# Driver_Controller_Tester.net
KiCad netlist of a schematic drawn in Altium Designer
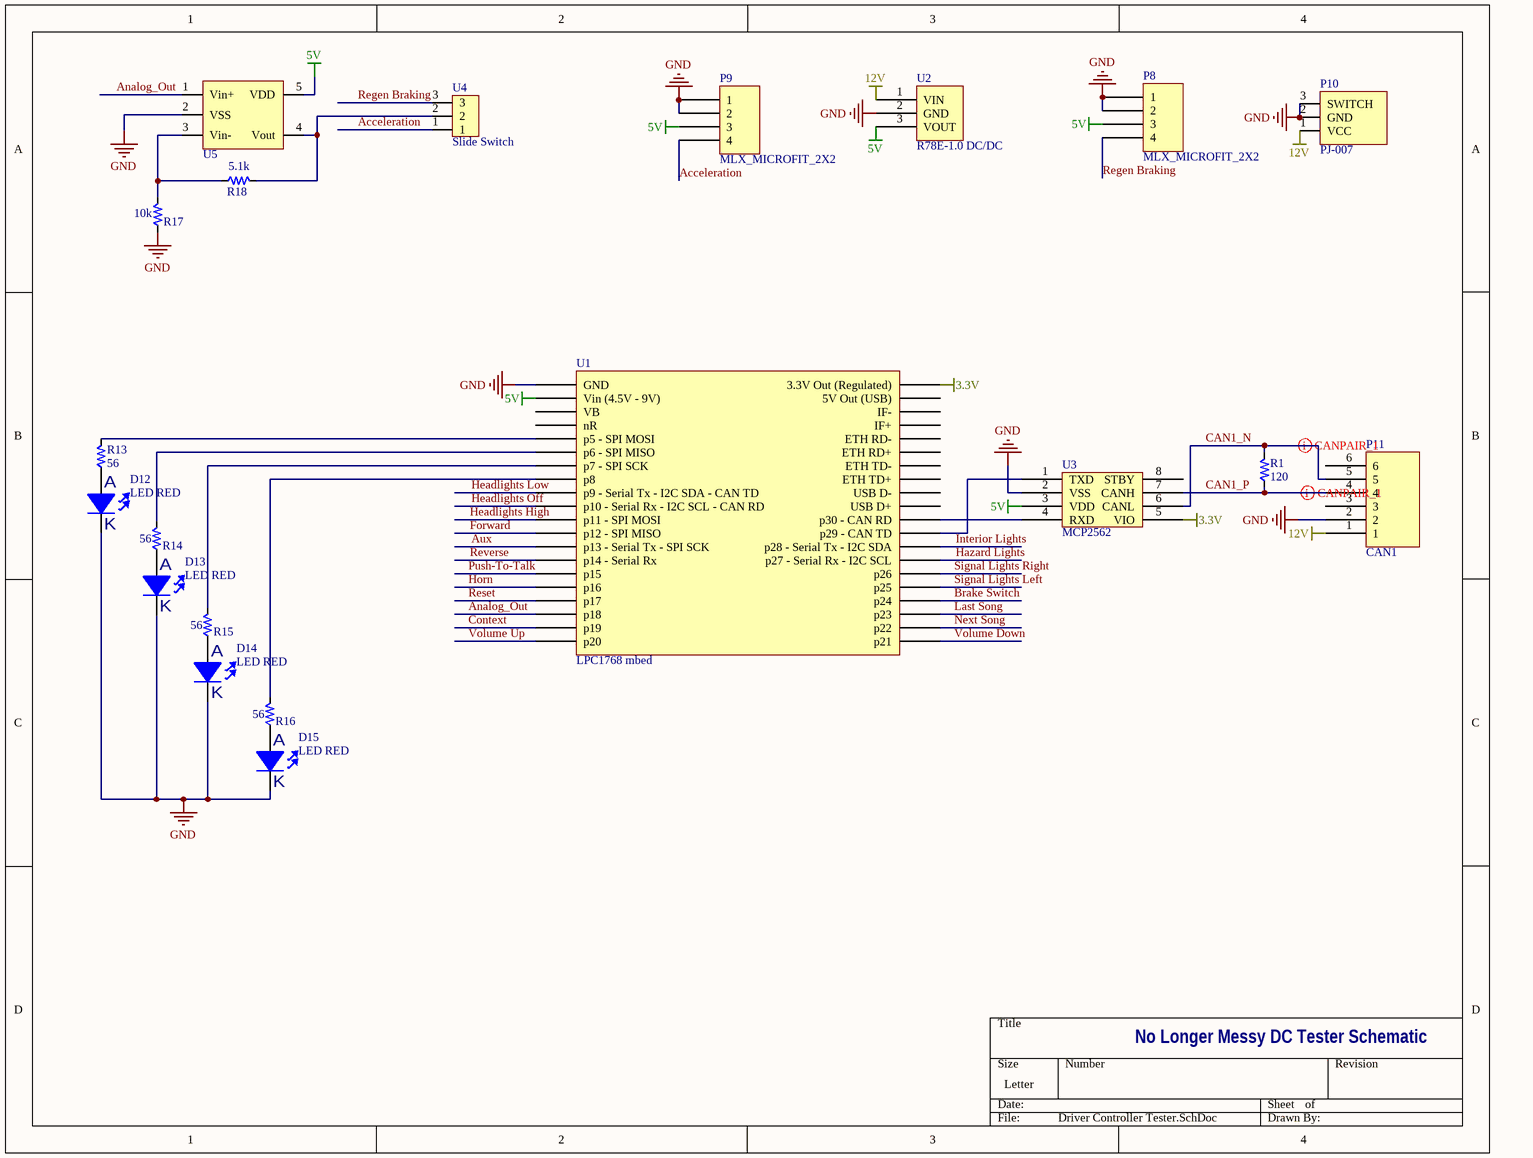
[diagram p0: Driver Controller Tester.SchDoc]

(export (version "E")
  (design (tool "Eeschema 10.0.6"))
  (components
    (comp (ref "D12")
      (value "LED RED")
      (footprint "RED LED")
      (libsource (lib "LED RED 150141RS73100") (part "LED RED"))
    )
    (comp (ref "D13")
      (value "LED RED")
      (footprint "RED LED")
      (libsource (lib "LED RED 150141RS73100") (part "LED RED"))
    )
    (comp (ref "D14")
      (value "LED RED")
      (footprint "RED LED")
      (libsource (lib "LED RED 150141RS73100") (part "LED RED"))
    )
    (comp (ref "D15")
      (value "LED RED")
      (footprint "RED LED")
      (libsource (lib "LED RED 150141RS73100") (part "LED RED"))
    )
    (comp (ref "P8")
      (value "MLX_MICROFIT_2X2")
      (footprint "MLX_MICROFIT_2X2")
      (libsource (lib "MLX_MICROFIT_2X2_SCH") (part "MLX_MICROFIT_2X2"))
    )
    (comp (ref "P9")
      (value "MLX_MICROFIT_2X2")
      (footprint "MLX_MICROFIT_2X2")
      (libsource (lib "MLX_MICROFIT_2X2_SCH") (part "MLX_MICROFIT_2X2"))
    )
    (comp (ref "P10")
      (value "PJ-007")
      (footprint "BARREL JACK PJ007")
      (libsource (lib "BARREL JACK PJ-007") (part "Component_1"))
    )
    (comp (ref "P11")
      (value "CAN1")
      (footprint "PCB_MLX_MICROFIT_3X2")
      (libsource (lib "SCH_MLX_MICROFIT_3X2_P") (part "SCH_MLX_MICROFIT_3X2"))
    )
    (comp (ref "R1")
      (value "120")
      (footprint "PCB_GENERIC_SMD_0603")
      (description "120 Ohms")
      (libsource (lib "SCH_GENERIC_RESISTOR_0603") (part "SCH_GENERIC_RESISTOR_0603"))
    )
    (comp (ref "R13")
      (value "SCH_GENERIC_RESISTOR_0603")
      (footprint "PCB_GENERIC_SMD_0603")
      (description "Generic SMD resistor 0603")
      (fields (field (name "RESISTANCE") "56"))
      (libsource (lib "SCH_GENERIC_RESISTOR_0603") (part "SCH_GENERIC_RESISTOR_0603"))
    )
    (comp (ref "R14")
      (value "SCH_GENERIC_RESISTOR_0603")
      (footprint "PCB_GENERIC_SMD_0603")
      (description "Generic SMD resistor 0603")
      (fields (field (name "RESISTANCE") "56"))
      (libsource (lib "SCH_GENERIC_RESISTOR_0603") (part "SCH_GENERIC_RESISTOR_0603"))
    )
    (comp (ref "R15")
      (value "SCH_GENERIC_RESISTOR_0603")
      (footprint "PCB_GENERIC_SMD_0603")
      (description "Generic SMD resistor 0603")
      (fields (field (name "RESISTANCE") "56"))
      (libsource (lib "SCH_GENERIC_RESISTOR_0603") (part "SCH_GENERIC_RESISTOR_0603"))
    )
    (comp (ref "R16")
      (value "SCH_GENERIC_RESISTOR_0603")
      (footprint "PCB_GENERIC_SMD_0603")
      (description "Generic SMD resistor 0603")
      (fields (field (name "RESISTANCE") "56"))
      (libsource (lib "SCH_GENERIC_RESISTOR_0603") (part "SCH_GENERIC_RESISTOR_0603"))
    )
    (comp (ref "R17")
      (value "SCH_GENERIC_RESISTOR_0603")
      (footprint "PCB_GENERIC_SMD_0603")
      (description "Generic SMD resistor 0603")
      (fields (field (name "RESISTANCE") "10k"))
      (libsource (lib "SCH_GENERIC_RESISTOR_0603") (part "SCH_GENERIC_RESISTOR_0603"))
    )
    (comp (ref "R18")
      (value "SCH_GENERIC_RESISTOR_0603")
      (footprint "PCB_GENERIC_SMD_0603")
      (description "Generic SMD resistor 0603")
      (fields (field (name "RESISTANCE") "5.1k"))
      (libsource (lib "SCH_GENERIC_RESISTOR_0603") (part "SCH_GENERIC_RESISTOR_0603"))
    )
    (comp (ref "U1")
      (value "LPC1768 mbed")
      (footprint "LPC 1768 mbed Layout")
      (libsource (lib "LPC1768_mbed_SCH") (part "LPC1768 mbed"))
    )
    (comp (ref "U2")
      (value "R78E-1.0 DC/DC")
      (footprint "R78-1.0")
      (libsource (lib "R78E-1.0_DCDC_SCH") (part "R78E-1.0"))
    )
    (comp (ref "U3") (value "MCP2562") (footprint "MCP2562") (libsource (lib "MCP2562_SCH") (part "MCP2562")))
    (comp (ref "U4")
      (value "Slide Switch")
      (footprint "Slide Switch")
      (libsource (lib "Slide Switch") (part "Slide Switch"))
    )
    (comp (ref "U5")
      (value "MCP6001U")
      (footprint "MCP6001UT")
      (libsource (lib "Op Amp MCP6001UT") (part "MCP6001U"))
    )
  )
  (nets
    (net (code "1") (name "/Acceleration") (class "Default")
      (node (ref "P9") (pin "4") (pinfunction "4_4") (pintype "passive"))
      (node (ref "U4") (pin "1") (pinfunction "1_1") (pintype "passive"))
    )
    (net (code "2") (name "/Analog_Out") (class "Default")
      (node (ref "U1") (pin "18") (pinfunction "p18_18") (pintype "passive"))
      (node (ref "U5") (pin "1") (pinfunction "Vin+_1") (pintype "passive"))
    )
    (net (code "3") (name "/Aux") (class "Default")
      (node (ref "U1") (pin "13") (pinfunction "p13_-_Serial_Tx_-_SPI_SCK_13") (pintype "passive"))
    )
    (net (code "4") (name "/Brake Switch") (class "Default")
      (node (ref "U1") (pin "24") (pinfunction "p24_24") (pintype "passive"))
    )
    (net (code "5") (name "/CAN1_N") (class "Default")
      (node (ref "P11") (pin "5") (pinfunction "5_5") (pintype "passive"))
      (node (ref "R1") (pin "2") (pinfunction "2_2") (pintype "passive"))
      (node (ref "U3") (pin "6") (pinfunction "CANL_6") (pintype "passive"))
    )
    (net (code "6") (name "/CAN1_P") (class "Default")
      (node (ref "P11") (pin "4") (pinfunction "4_4") (pintype "passive"))
      (node (ref "R1") (pin "1") (pinfunction "1_1") (pintype "passive"))
      (node (ref "U3") (pin "7") (pinfunction "CANH_7") (pintype "passive"))
    )
    (net (code "7") (name "/Context") (class "Default")
      (node (ref "U1") (pin "19") (pinfunction "p19_19") (pintype "passive"))
    )
    (net (code "8") (name "/Forward") (class "Default")
      (node (ref "U1") (pin "12") (pinfunction "p12_-_SPI_MISO_12") (pintype "passive"))
    )
    (net (code "9") (name "/Hazard Lights") (class "Default")
      (node (ref "U1") (pin "27") (pinfunction "p27_-_Serial_Rx_-_I2C_SCL_27") (pintype "passive"))
    )
    (net (code "10") (name "/Headlights High") (class "Default")
      (node (ref "U1") (pin "11") (pinfunction "p11_-_SPI_MOSI_11") (pintype "passive"))
    )
    (net (code "11") (name "/Headlights Low") (class "Default")
      (node (ref "U1") (pin "9") (pinfunction "p9_-_Serial_Tx_-_I2C_SDA_-_CAN_TD_9") (pintype "passive"))
    )
    (net (code "12") (name "/Headlights Off") (class "Default")
      (node (ref "U1") (pin "10") (pinfunction "p10_-_Serial_Rx_-_I2C_SCL_-_CAN_RD_10") (pintype "passive"))
    )
    (net (code "13") (name "/Horn") (class "Default")
      (node (ref "U1") (pin "16") (pinfunction "p16_16") (pintype "passive"))
    )
    (net (code "14") (name "/Interior Lights") (class "Default")
      (node (ref "U1") (pin "28") (pinfunction "p28_-_Serial_Tx_-_I2C_SDA_28") (pintype "passive"))
    )
    (net (code "15") (name "/Last Song") (class "Default")
      (node (ref "U1") (pin "23") (pinfunction "p23_23") (pintype "passive"))
    )
    (net (code "16") (name "/Next Song") (class "Default")
      (node (ref "U1") (pin "22") (pinfunction "p22_22") (pintype "passive"))
    )
    (net (code "17") (name "/Push-To-Talk") (class "Default")
      (node (ref "U1") (pin "15") (pinfunction "p15_15") (pintype "passive"))
    )
    (net (code "18") (name "/Regen Braking") (class "Default")
      (node (ref "P8") (pin "4") (pinfunction "4_4") (pintype "passive"))
      (node (ref "U4") (pin "3") (pinfunction "3_3") (pintype "passive"))
    )
    (net (code "19") (name "/Reset") (class "Default")
      (node (ref "U1") (pin "17") (pinfunction "p17_17") (pintype "passive"))
    )
    (net (code "20") (name "/Reverse") (class "Default")
      (node (ref "U1") (pin "14") (pinfunction "p14_-_Serial_Rx_14") (pintype "passive"))
    )
    (net (code "21") (name "/Signal Lights Left") (class "Default")
      (node (ref "U1") (pin "25") (pinfunction "p25_25") (pintype "passive"))
    )
    (net (code "22") (name "/Signal Lights Right") (class "Default")
      (node (ref "U1") (pin "26") (pinfunction "p26_26") (pintype "passive"))
    )
    (net (code "23") (name "/Volume Down") (class "Default")
      (node (ref "U1") (pin "21") (pinfunction "p21_21") (pintype "passive"))
    )
    (net (code "24") (name "/Volume Up") (class "Default")
      (node (ref "U1") (pin "20") (pinfunction "p20_20") (pintype "passive"))
    )
    (net (code "25") (name "3.3V") (class "Default")
      (node (ref "U1") (pin "40") (pinfunction "3.3V_Out_(Regulated)_40") (pintype "passive"))
      (node (ref "U3") (pin "5") (pinfunction "VIO_5") (pintype "passive"))
    )
    (net (code "26") (name "5V") (class "Default")
      (node (ref "P8") (pin "3") (pinfunction "3_3") (pintype "passive"))
      (node (ref "P9") (pin "3") (pinfunction "3_3") (pintype "passive"))
      (node (ref "U1") (pin "2") (pinfunction "Vin_(4.5V_-_9V)_2") (pintype "passive"))
      (node (ref "U2") (pin "3") (pinfunction "VOUT_3") (pintype "passive"))
      (node (ref "U3") (pin "3") (pinfunction "VDD_3") (pintype "passive"))
      (node (ref "U5") (pin "5") (pinfunction "VDD_5") (pintype "passive"))
    )
    (net (code "27") (name "12V") (class "Default")
      (node (ref "P10") (pin "1") (pinfunction "VCC_1") (pintype "passive"))
      (node (ref "P11") (pin "1") (pinfunction "1_1") (pintype "passive"))
      (node (ref "U2") (pin "1") (pinfunction "VIN_1") (pintype "passive"))
    )
    (net (code "28") (name "GND") (class "Default")
      (node (ref "D12") (pin "1") (pintype "passive"))
      (node (ref "D13") (pin "1") (pintype "passive"))
      (node (ref "D14") (pin "1") (pintype "passive"))
      (node (ref "D15") (pin "1") (pintype "passive"))
      (node (ref "P10") (pin "2") (pinfunction "GND_2") (pintype "passive"))
      (node (ref "P10") (pin "3") (pinfunction "SWITCH_3") (pintype "passive"))
      (node (ref "P11") (pin "2") (pinfunction "2_2") (pintype "passive"))
      (node (ref "P8") (pin "1") (pinfunction "1_1") (pintype "passive"))
      (node (ref "P8") (pin "2") (pinfunction "2_2") (pintype "passive"))
      (node (ref "P9") (pin "1") (pinfunction "1_1") (pintype "passive"))
      (node (ref "P9") (pin "2") (pinfunction "2_2") (pintype "passive"))
      (node (ref "R17") (pin "1") (pinfunction "1_1") (pintype "passive"))
      (node (ref "U1") (pin "1") (pinfunction "GND_1") (pintype "passive"))
      (node (ref "U2") (pin "2") (pinfunction "GND_2") (pintype "passive"))
      (node (ref "U3") (pin "2") (pinfunction "VSS_2") (pintype "passive"))
      (node (ref "U5") (pin "2") (pinfunction "VSS_2") (pintype "passive"))
    )
    (net (code "29") (name "Net-(D12-Pad2)") (class "Default")
      (node (ref "D12") (pin "2") (pintype "passive"))
      (node (ref "R13") (pin "1") (pinfunction "1_1") (pintype "passive"))
    )
    (net (code "30") (name "Net-(D13-Pad2)") (class "Default")
      (node (ref "D13") (pin "2") (pintype "passive"))
      (node (ref "R14") (pin "1") (pinfunction "1_1") (pintype "passive"))
    )
    (net (code "31") (name "Net-(D14-Pad2)") (class "Default")
      (node (ref "D14") (pin "2") (pintype "passive"))
      (node (ref "R15") (pin "1") (pinfunction "1_1") (pintype "passive"))
    )
    (net (code "32") (name "Net-(D15-Pad2)") (class "Default")
      (node (ref "D15") (pin "2") (pintype "passive"))
      (node (ref "R16") (pin "1") (pinfunction "1_1") (pintype "passive"))
    )
    (net (code "33") (name "Net-(U1-p5_-_SPI_MOSI)") (class "Default")
      (node (ref "R13") (pin "2") (pinfunction "2_2") (pintype "passive"))
      (node (ref "U1") (pin "5") (pinfunction "p5_-_SPI_MOSI_5") (pintype "passive"))
    )
    (net (code "34") (name "Net-(U1-p6_-_SPI_MISO)") (class "Default")
      (node (ref "R14") (pin "2") (pinfunction "2_2") (pintype "passive"))
      (node (ref "U1") (pin "6") (pinfunction "p6_-_SPI_MISO_6") (pintype "passive"))
    )
    (net (code "35") (name "Net-(U1-p7_-_SPI_SCK)") (class "Default")
      (node (ref "R15") (pin "2") (pinfunction "2_2") (pintype "passive"))
      (node (ref "U1") (pin "7") (pinfunction "p7_-_SPI_SCK_7") (pintype "passive"))
    )
    (net (code "36") (name "Net-(U1-p8)") (class "Default")
      (node (ref "R16") (pin "2") (pinfunction "2_2") (pintype "passive"))
      (node (ref "U1") (pin "8") (pinfunction "p8_8") (pintype "passive"))
    )
    (net (code "37") (name "Net-(U1-p29_-_CAN_TD)") (class "Default")
      (node (ref "U1") (pin "29") (pinfunction "p29_-_CAN_TD_29") (pintype "passive"))
      (node (ref "U3") (pin "1") (pinfunction "TXD_1") (pintype "passive"))
    )
    (net (code "38") (name "Net-(U1-p30_-_CAN_RD)") (class "Default")
      (node (ref "U1") (pin "30") (pinfunction "p30_-_CAN_RD_30") (pintype "passive"))
      (node (ref "U3") (pin "4") (pinfunction "RXD_4") (pintype "passive"))
    )
    (net (code "39") (name "Net-(U5-Vin-)") (class "Default")
      (node (ref "R17") (pin "2") (pinfunction "2_2") (pintype "passive"))
      (node (ref "R18") (pin "1") (pinfunction "1_1") (pintype "passive"))
      (node (ref "U5") (pin "3") (pinfunction "Vin-_3") (pintype "passive"))
    )
    (net (code "40") (name "Net-(U5-Vout)") (class "Default")
      (node (ref "R18") (pin "2") (pinfunction "2_2") (pintype "passive"))
      (node (ref "U4") (pin "2") (pinfunction "2_2") (pintype "passive"))
      (node (ref "U5") (pin "4") (pinfunction "Vout_4") (pintype "passive"))
    )
    (net (code "41") (name "unconnected-(P11-Pad3)") (class "Default")
      (node (ref "P11") (pin "3") (pinfunction "3_3") (pintype "passive"))
    )
    (net (code "42") (name "unconnected-(P11-Pad6)") (class "Default")
      (node (ref "P11") (pin "6") (pinfunction "6_6") (pintype "passive"))
    )
    (net (code "43") (name "unconnected-(U1-5V_Out_(USB)-Pad39)") (class "Default")
      (node (ref "U1") (pin "39") (pinfunction "5V_Out_(USB)_39") (pintype "passive"))
    )
    (net (code "44") (name "unconnected-(U1-ETH_RD+-Pad35)") (class "Default")
      (node (ref "U1") (pin "35") (pinfunction "ETH_RD+_35") (pintype "passive"))
    )
    (net (code "45") (name "unconnected-(U1-ETH_RD--Pad36)") (class "Default")
      (node (ref "U1") (pin "36") (pinfunction "ETH_RD-_36") (pintype "passive"))
    )
    (net (code "46") (name "unconnected-(U1-ETH_TD+-Pad33)") (class "Default")
      (node (ref "U1") (pin "33") (pinfunction "ETH_TD+_33") (pintype "passive"))
    )
    (net (code "47") (name "unconnected-(U1-ETH_TD--Pad34)") (class "Default")
      (node (ref "U1") (pin "34") (pinfunction "ETH_TD-_34") (pintype "passive"))
    )
    (net (code "48") (name "unconnected-(U1-IF+-Pad37)") (class "Default")
      (node (ref "U1") (pin "37") (pinfunction "IF+_37") (pintype "passive"))
    )
    (net (code "49") (name "unconnected-(U1-IF--Pad38)") (class "Default")
      (node (ref "U1") (pin "38") (pinfunction "IF-_38") (pintype "passive"))
    )
    (net (code "50") (name "unconnected-(U1-USB_D+-Pad31)") (class "Default")
      (node (ref "U1") (pin "31") (pinfunction "USB_D+_31") (pintype "passive"))
    )
    (net (code "51") (name "unconnected-(U1-USB_D--Pad32)") (class "Default")
      (node (ref "U1") (pin "32") (pinfunction "USB_D-_32") (pintype "passive"))
    )
    (net (code "52") (name "unconnected-(U1-VB-Pad3)") (class "Default")
      (node (ref "U1") (pin "3") (pinfunction "VB_3") (pintype "passive"))
    )
    (net (code "53") (name "unconnected-(U1-nR-Pad4)") (class "Default")
      (node (ref "U1") (pin "4") (pinfunction "nR_4") (pintype "passive"))
    )
    (net (code "54") (name "unconnected-(U3-STBY-Pad8)") (class "Default")
      (node (ref "U3") (pin "8") (pinfunction "STBY_8") (pintype "passive"))
    )
  )
)
